# SCH_03_Instrumentation_Amplifier.net
KiCad netlist of a schematic drawn in Altium Designer
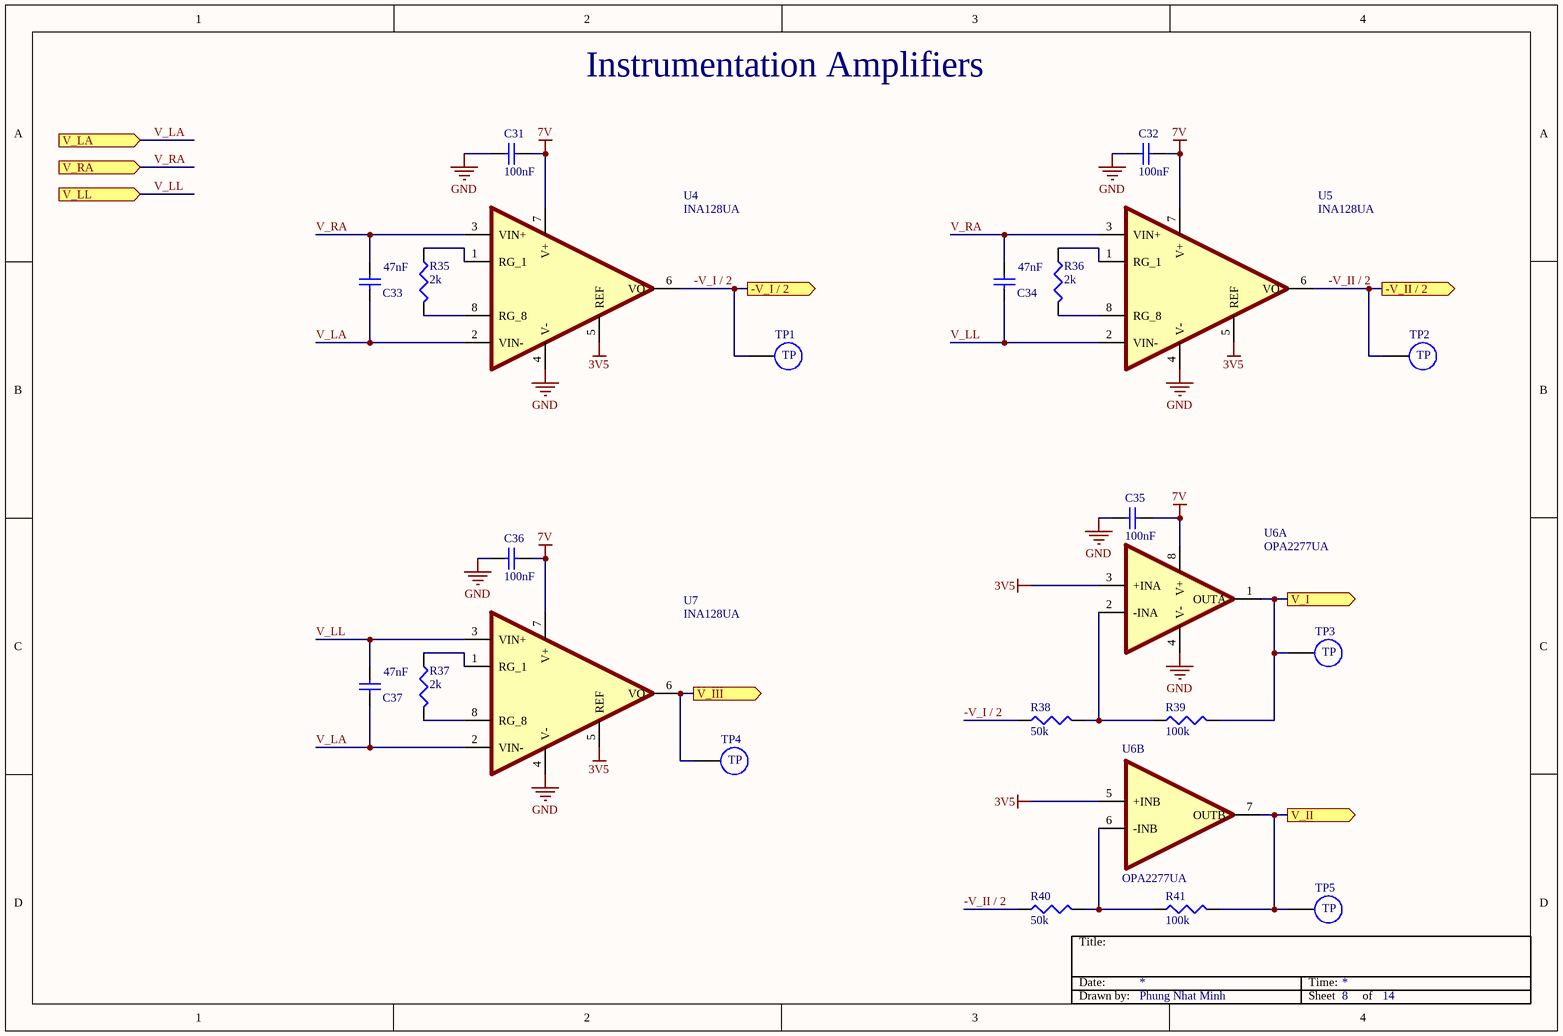
[diagram p0: SCH_03_Instrumentation_Amplifier.SchDoc]

(export (version "E")
  (design (tool "Eeschema 10.0.6"))
  (components
    (comp (ref "C31")
      (value "100nF")
      (footprint "WCAP-CSGP_0603_L1.6W0.8H0.8_Reflow")
      (description "WCAP-CSGP Multilayer Ceramic Chip Capacitor, General Purpose, size 0603, X7R, 100nF, 50VDC")
      (fields
        (field (name "MANUFACTURER PART NUMBER") "885012206095")
        (field (name "MANUFACTURER") "Wurth Elektronik")
      )
      (libsource (lib "Altium_WCAP-CSGP (rev24b)") (part "885012206095"))
    )
    (comp (ref "C32")
      (value "100nF")
      (footprint "WCAP-CSGP_0603_L1.6W0.8H0.8_Reflow")
      (description "WCAP-CSGP Multilayer Ceramic Chip Capacitor, General Purpose, size 0603, X7R, 100nF, 50VDC")
      (fields
        (field (name "MANUFACTURER PART NUMBER") "885012206095")
        (field (name "MANUFACTURER") "Wurth Elektronik")
      )
      (libsource (lib "Altium_WCAP-CSGP (rev24b)") (part "885012206095"))
    )
    (comp (ref "C33")
      (value "47nF")
      (footprint "WCAP-CSGP_0603_L1.6W0.8H0.8_Reflow")
      (description "WCAP-CSGP Multilayer Ceramic Chip Capacitor, General Purpose, size 0603, X7R, 47nF, 50VDC")
      (fields
        (field (name "MANUFACTURER PART NUMBER") "885012206093")
        (field (name "MANUFACTURER") "Wurth Elektronik")
      )
      (libsource (lib "Altium_WCAP-CSGP (rev24b)") (part "885012206093"))
    )
    (comp (ref "C34")
      (value "47nF")
      (footprint "WCAP-CSGP_0603_L1.6W0.8H0.8_Reflow")
      (description "WCAP-CSGP Multilayer Ceramic Chip Capacitor, General Purpose, size 0603, X7R, 47nF, 50VDC")
      (fields
        (field (name "MANUFACTURER PART NUMBER") "885012206093")
        (field (name "MANUFACTURER") "Wurth Elektronik")
      )
      (libsource (lib "Altium_WCAP-CSGP (rev24b)") (part "885012206093"))
    )
    (comp (ref "C35")
      (value "100nF")
      (footprint "WCAP-CSGP_0603_L1.6W0.8H0.8_Reflow")
      (description "WCAP-CSGP Multilayer Ceramic Chip Capacitor, General Purpose, size 0603, X7R, 100nF, 50VDC")
      (fields
        (field (name "MANUFACTURER PART NUMBER") "885012206095")
        (field (name "MANUFACTURER") "Wurth Elektronik")
      )
      (libsource (lib "Altium_WCAP-CSGP (rev24b)") (part "885012206095"))
    )
    (comp (ref "C36")
      (value "100nF")
      (footprint "WCAP-CSGP_0603_L1.6W0.8H0.8_Reflow")
      (description "WCAP-CSGP Multilayer Ceramic Chip Capacitor, General Purpose, size 0603, X7R, 100nF, 50VDC")
      (fields
        (field (name "MANUFACTURER PART NUMBER") "885012206095")
        (field (name "MANUFACTURER") "Wurth Elektronik")
      )
      (libsource (lib "Altium_WCAP-CSGP (rev24b)") (part "885012206095"))
    )
    (comp (ref "C37")
      (value "47nF")
      (footprint "WCAP-CSGP_0603_L1.6W0.8H0.8_Reflow")
      (description "WCAP-CSGP Multilayer Ceramic Chip Capacitor, General Purpose, size 0603, X7R, 47nF, 50VDC")
      (fields
        (field (name "MANUFACTURER PART NUMBER") "885012206093")
        (field (name "MANUFACTURER") "Wurth Elektronik")
      )
      (libsource (lib "Altium_WCAP-CSGP (rev24b)") (part "885012206093"))
    )
    (comp (ref "R35")
      (value "2k")
      (footprint "WRIS-PSMB_0603_L1.6W0.8H0.35")
      (description "WRIS-PSMB Metal Plate Resistor, SMT, size 0603, 0.33W, 5mΩ, +/-1%")
      (fields
        (field (name "MANUFACTURER PART NUMBER") "580060716001")
        (field (name "MANUFACTURER") "Wurth Elektronik")
      )
      (libsource (lib "Altium_WRIS-PSMB (rev22a)") (part "580060716001"))
    )
    (comp (ref "R36")
      (value "2k")
      (footprint "WRIS-PSMB_0603_L1.6W0.8H0.35")
      (description "WRIS-PSMB Metal Plate Resistor, SMT, size 0603, 0.33W, 5mΩ, +/-1%")
      (fields
        (field (name "MANUFACTURER PART NUMBER") "580060716001")
        (field (name "MANUFACTURER") "Wurth Elektronik")
      )
      (libsource (lib "Altium_WRIS-PSMB (rev22a)") (part "580060716001"))
    )
    (comp (ref "R37")
      (value "2k")
      (footprint "WRIS-PSMB_0603_L1.6W0.8H0.35")
      (description "WRIS-PSMB Metal Plate Resistor, SMT, size 0603, 0.33W, 5mΩ, +/-1%")
      (fields
        (field (name "MANUFACTURER PART NUMBER") "580060716001")
        (field (name "MANUFACTURER") "Wurth Elektronik")
      )
      (libsource (lib "Altium_WRIS-PSMB (rev22a)") (part "580060716001"))
    )
    (comp (ref "R38")
      (value "50k")
      (footprint "WRIS-PSMB_0603_L1.6W0.8H0.35")
      (description "WRIS-PSMB Metal Plate Resistor, SMT, size 0603, 0.33W, 5mΩ, +/-1%")
      (fields
        (field (name "MANUFACTURER PART NUMBER") "580060716001")
        (field (name "MANUFACTURER") "Wurth Elektronik")
      )
      (libsource (lib "Altium_WRIS-PSMB (rev22a)") (part "580060716001"))
    )
    (comp (ref "R39")
      (value "100k")
      (footprint "WRIS-PSMB_0603_L1.6W0.8H0.35")
      (description "WRIS-PSMB Metal Plate Resistor, SMT, size 0603, 0.33W, 5mΩ, +/-1%")
      (fields
        (field (name "MANUFACTURER PART NUMBER") "580060716001")
        (field (name "MANUFACTURER") "Wurth Elektronik")
      )
      (libsource (lib "Altium_WRIS-PSMB (rev22a)") (part "580060716001"))
    )
    (comp (ref "R40")
      (value "50k")
      (footprint "WRIS-PSMB_0603_L1.6W0.8H0.35")
      (description "WRIS-PSMB Metal Plate Resistor, SMT, size 0603, 0.33W, 5mΩ, +/-1%")
      (fields
        (field (name "MANUFACTURER PART NUMBER") "580060716001")
        (field (name "MANUFACTURER") "Wurth Elektronik")
      )
      (libsource (lib "Altium_WRIS-PSMB (rev22a)") (part "580060716001"))
    )
    (comp (ref "R41")
      (value "100k")
      (footprint "WRIS-PSMB_0603_L1.6W0.8H0.35")
      (description "WRIS-PSMB Metal Plate Resistor, SMT, size 0603, 0.33W, 5mΩ, +/-1%")
      (fields
        (field (name "MANUFACTURER PART NUMBER") "580060716001")
        (field (name "MANUFACTURER") "Wurth Elektronik")
      )
      (libsource (lib "Altium_WRIS-PSMB (rev22a)") (part "580060716001"))
    )
    (comp (ref "TP1")
      (value "Pad_Test_Point")
      (footprint "Pad_Test_Point")
      (libsource (lib "Test_Point") (part "Pad_Test_Point"))
    )
    (comp (ref "TP2")
      (value "Pad_Test_Point")
      (footprint "Pad_Test_Point")
      (libsource (lib "Test_Point") (part "Pad_Test_Point"))
    )
    (comp (ref "TP3")
      (value "Pad_Test_Point")
      (footprint "Pad_Test_Point")
      (libsource (lib "Test_Point") (part "Pad_Test_Point"))
    )
    (comp (ref "TP4")
      (value "Pad_Test_Point")
      (footprint "Pad_Test_Point")
      (libsource (lib "Test_Point") (part "Pad_Test_Point"))
    )
    (comp (ref "TP5")
      (value "Pad_Test_Point")
      (footprint "Pad_Test_Point")
      (libsource (lib "Test_Point") (part "Pad_Test_Point"))
    )
    (comp (ref "U4")
      (value "INA128UA")
      (footprint "SOIC127P599X175-8N")
      (description "Precision, 130-dB CMRR, 700-A, Low-Power, Instrumentation Amplifier 8-SOIC -40 to 125")
      (fields (field (name "MP") "INA128UA/2K5") (field (name "MF") "Texas Instruments"))
      (libsource (lib "INA128UA") (part "INA128UA"))
    )
    (comp (ref "U5")
      (value "INA128UA")
      (footprint "SOIC127P599X175-8N")
      (description "Precision, 130-dB CMRR, 700-A, Low-Power, Instrumentation Amplifier 8-SOIC -40 to 125")
      (fields (field (name "MP") "INA128UA/2K5") (field (name "MF") "Texas Instruments"))
      (libsource (lib "INA128UA") (part "INA128UA"))
    )
    (comp (ref "U6")
      (value "OPA2277UA")
      (footprint "SOIC127P599X175-8N")
      (fields (field (name "MP") "OPA2227UA"))
      (libsource (lib "OPA2277") (part "OPA2277UA"))
    )
    (comp (ref "U7")
      (value "INA128UA")
      (footprint "SOIC127P599X175-8N")
      (description "Precision, 130-dB CMRR, 700-A, Low-Power, Instrumentation Amplifier 8-SOIC -40 to 125")
      (fields (field (name "MP") "INA128UA/2K5") (field (name "MF") "Texas Instruments"))
      (libsource (lib "INA128UA") (part "INA128UA"))
    )
  )
  (nets
    (net (code "1") (name "/-V_I {slash} 2") (class "Default")
      (node (ref "R38") (pin "1") (pinfunction "1_1") (pintype "passive"))
      (node (ref "TP1") (pin "1") (pinfunction "1_1") (pintype "passive"))
      (node (ref "U4") (pin "6") (pinfunction "VO_6") (pintype "passive"))
    )
    (net (code "2") (name "/-V_II {slash} 2") (class "Default")
      (node (ref "R40") (pin "1") (pinfunction "1_1") (pintype "passive"))
      (node (ref "TP2") (pin "1") (pinfunction "1_1") (pintype "passive"))
      (node (ref "U5") (pin "6") (pinfunction "VO_6") (pintype "passive"))
    )
    (net (code "3") (name "/V_I") (class "Default")
      (node (ref "R39") (pin "2") (pinfunction "2_2") (pintype "passive"))
      (node (ref "TP3") (pin "1") (pinfunction "1_1") (pintype "passive"))
      (node (ref "U6") (pin "1") (pinfunction "OUTA_1") (pintype "passive"))
    )
    (net (code "4") (name "/V_II") (class "Default")
      (node (ref "R41") (pin "2") (pinfunction "2_2") (pintype "passive"))
      (node (ref "TP5") (pin "1") (pinfunction "1_1") (pintype "passive"))
      (node (ref "U6") (pin "7") (pinfunction "OUTB_7") (pintype "passive"))
    )
    (net (code "5") (name "/V_III") (class "Default")
      (node (ref "TP4") (pin "1") (pinfunction "1_1") (pintype "passive"))
      (node (ref "U7") (pin "6") (pinfunction "VO_6") (pintype "passive"))
    )
    (net (code "6") (name "/V_LA") (class "Default")
      (node (ref "C33") (pin "1") (pinfunction "1_1") (pintype "passive"))
      (node (ref "C37") (pin "1") (pinfunction "1_1") (pintype "passive"))
      (node (ref "U4") (pin "2") (pinfunction "VIN-_2") (pintype "passive"))
      (node (ref "U7") (pin "2") (pinfunction "VIN-_2") (pintype "passive"))
    )
    (net (code "7") (name "/V_LL") (class "Default")
      (node (ref "C34") (pin "1") (pinfunction "1_1") (pintype "passive"))
      (node (ref "C37") (pin "2") (pinfunction "2_2") (pintype "passive"))
      (node (ref "U5") (pin "2") (pinfunction "VIN-_2") (pintype "passive"))
      (node (ref "U7") (pin "3") (pinfunction "VIN+_3") (pintype "passive"))
    )
    (net (code "8") (name "/V_RA") (class "Default")
      (node (ref "C33") (pin "2") (pinfunction "2_2") (pintype "passive"))
      (node (ref "C34") (pin "2") (pinfunction "2_2") (pintype "passive"))
      (node (ref "U4") (pin "3") (pinfunction "VIN+_3") (pintype "passive"))
      (node (ref "U5") (pin "3") (pinfunction "VIN+_3") (pintype "passive"))
    )
    (net (code "9") (name "3V5") (class "Default")
      (node (ref "U4") (pin "5") (pinfunction "REF_5") (pintype "passive"))
      (node (ref "U5") (pin "5") (pinfunction "REF_5") (pintype "passive"))
      (node (ref "U6") (pin "3") (pinfunction "+INA_3") (pintype "passive"))
      (node (ref "U6") (pin "5") (pinfunction "+INB_5") (pintype "passive"))
      (node (ref "U7") (pin "5") (pinfunction "REF_5") (pintype "passive"))
    )
    (net (code "10") (name "7V") (class "Default")
      (node (ref "C31") (pin "1") (pinfunction "1_1") (pintype "passive"))
      (node (ref "C32") (pin "1") (pinfunction "1_1") (pintype "passive"))
      (node (ref "C35") (pin "1") (pinfunction "1_1") (pintype "passive"))
      (node (ref "C36") (pin "1") (pinfunction "1_1") (pintype "passive"))
      (node (ref "U4") (pin "7") (pinfunction "V+_7") (pintype "power_in"))
      (node (ref "U5") (pin "7") (pinfunction "V+_7") (pintype "power_in"))
      (node (ref "U6") (pin "8") (pinfunction "V+_8") (pintype "power_in"))
      (node (ref "U7") (pin "7") (pinfunction "V+_7") (pintype "power_in"))
    )
    (net (code "11") (name "GND") (class "Default")
      (node (ref "C31") (pin "2") (pinfunction "2_2") (pintype "passive"))
      (node (ref "C32") (pin "2") (pinfunction "2_2") (pintype "passive"))
      (node (ref "C35") (pin "2") (pinfunction "2_2") (pintype "passive"))
      (node (ref "C36") (pin "2") (pinfunction "2_2") (pintype "passive"))
      (node (ref "U4") (pin "4") (pinfunction "V-_4") (pintype "power_in"))
      (node (ref "U5") (pin "4") (pinfunction "V-_4") (pintype "power_in"))
      (node (ref "U6") (pin "4") (pinfunction "V-_4") (pintype "power_in"))
      (node (ref "U7") (pin "4") (pinfunction "V-_4") (pintype "power_in"))
    )
    (net (code "12") (name "Net-(U4-RG_1)") (class "Default")
      (node (ref "R35") (pin "1") (pinfunction "1_1") (pintype "passive"))
      (node (ref "U4") (pin "1") (pinfunction "RG_1_1") (pintype "passive"))
    )
    (net (code "13") (name "Net-(U4-RG_8)") (class "Default")
      (node (ref "R35") (pin "2") (pinfunction "2_2") (pintype "passive"))
      (node (ref "U4") (pin "8") (pinfunction "RG_8_8") (pintype "passive"))
    )
    (net (code "14") (name "Net-(U5-RG_1)") (class "Default")
      (node (ref "R36") (pin "1") (pinfunction "1_1") (pintype "passive"))
      (node (ref "U5") (pin "1") (pinfunction "RG_1_1") (pintype "passive"))
    )
    (net (code "15") (name "Net-(U5-RG_8)") (class "Default")
      (node (ref "R36") (pin "2") (pinfunction "2_2") (pintype "passive"))
      (node (ref "U5") (pin "8") (pinfunction "RG_8_8") (pintype "passive"))
    )
    (net (code "16") (name "Net-(U6A--INA)") (class "Default")
      (node (ref "R38") (pin "2") (pinfunction "2_2") (pintype "passive"))
      (node (ref "R39") (pin "1") (pinfunction "1_1") (pintype "passive"))
      (node (ref "U6") (pin "2") (pinfunction "-INA_2") (pintype "passive"))
    )
    (net (code "17") (name "Net-(U6B--INB)") (class "Default")
      (node (ref "R40") (pin "2") (pinfunction "2_2") (pintype "passive"))
      (node (ref "R41") (pin "1") (pinfunction "1_1") (pintype "passive"))
      (node (ref "U6") (pin "6") (pinfunction "-INB_6") (pintype "passive"))
    )
    (net (code "18") (name "Net-(U7-RG_1)") (class "Default")
      (node (ref "R37") (pin "1") (pinfunction "1_1") (pintype "passive"))
      (node (ref "U7") (pin "1") (pinfunction "RG_1_1") (pintype "passive"))
    )
    (net (code "19") (name "Net-(U7-RG_8)") (class "Default")
      (node (ref "R37") (pin "2") (pinfunction "2_2") (pintype "passive"))
      (node (ref "U7") (pin "8") (pinfunction "RG_8_8") (pintype "passive"))
    )
  )
)
